# DOORLOCK_v4.net
KiCad netlist of a schematic drawn in EAGLE
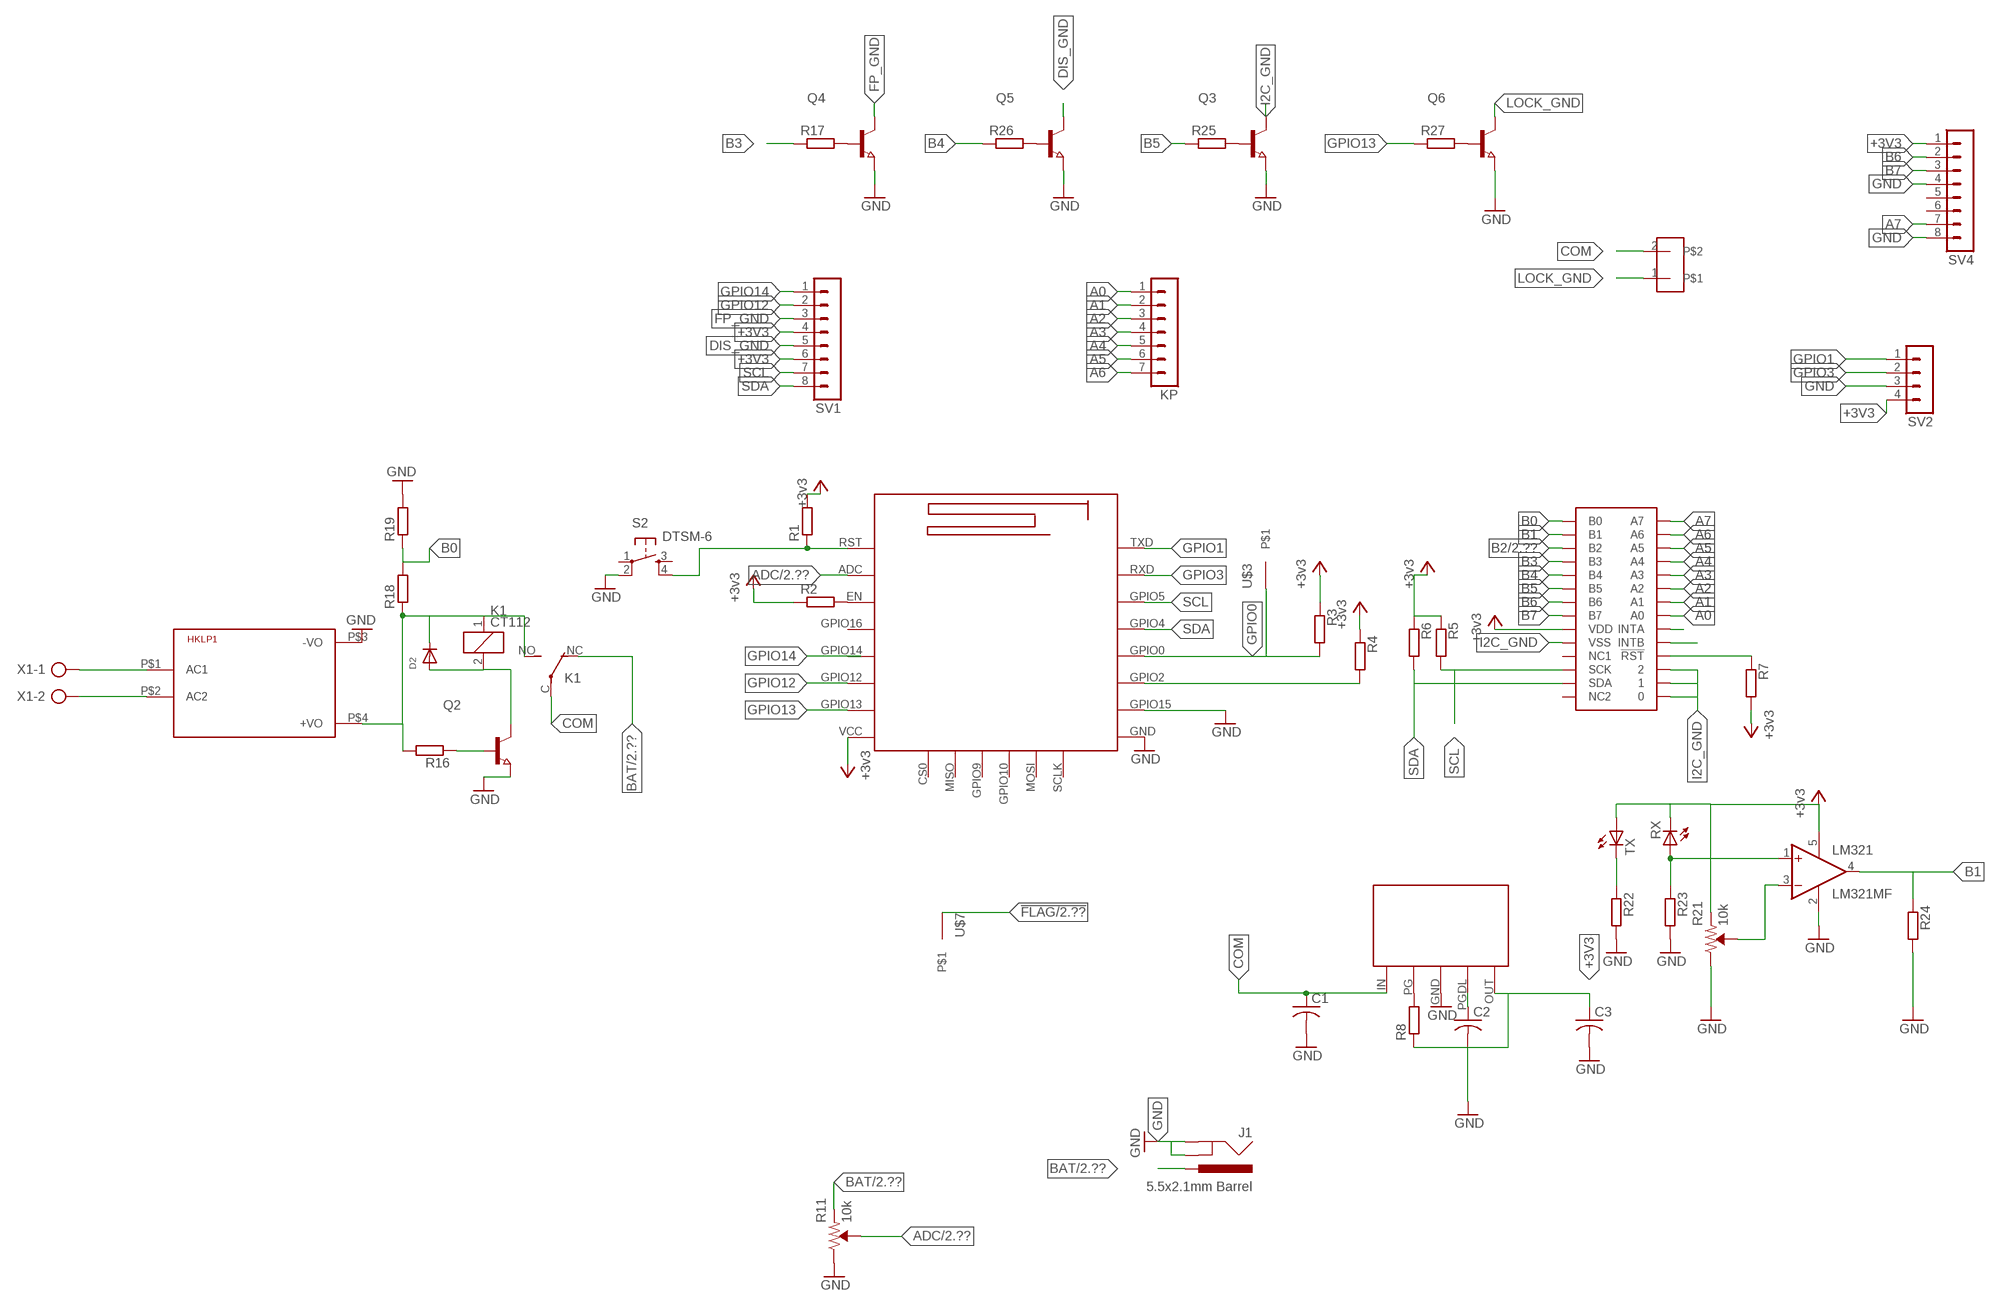
[diagram p0: schematic, sheet 1]
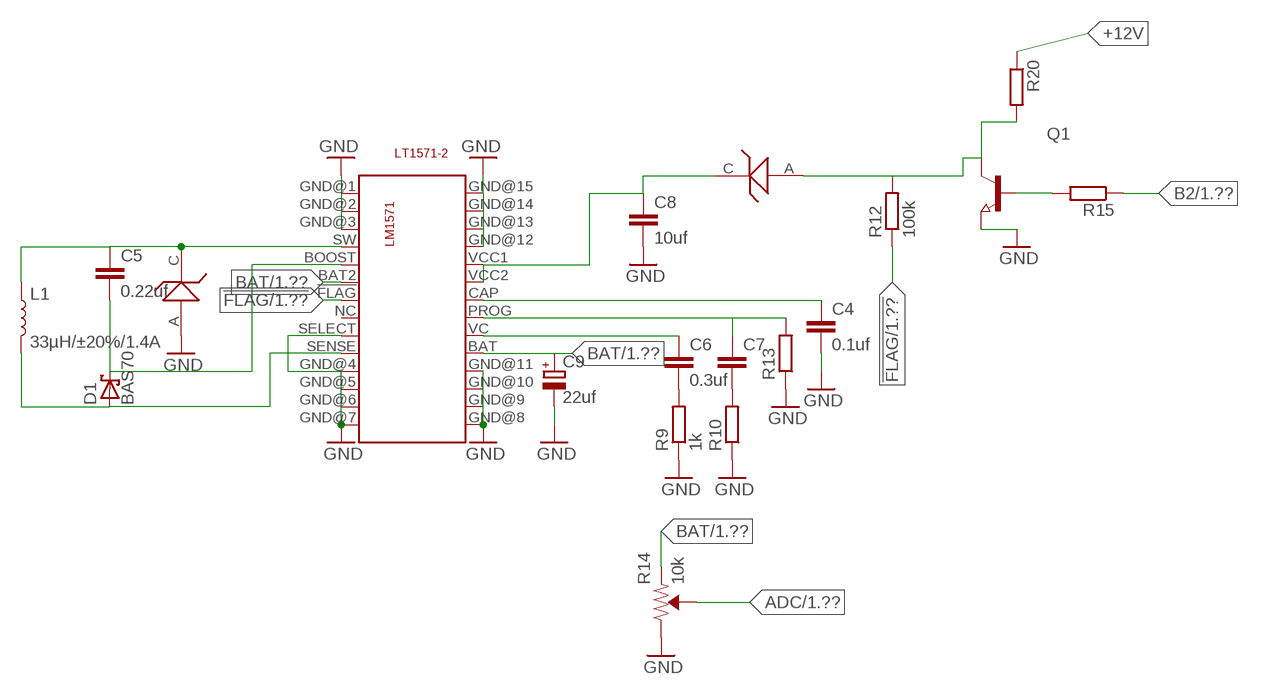
[diagram p1: schematic, sheet 2]

(export (version "E")
  (design (tool "Eeschema 10.0.6"))
  (components
    (comp (ref "C4")
      (value "0.1uf")
      (footprint "eagle-import:C0805")
      (libsource (lib "eagle-import") (part "C-EUC0805"))
    )
    (comp (ref "C5")
      (value "0.22uf")
      (footprint "eagle-import:C0805")
      (libsource (lib "eagle-import") (part "C-EUC0805"))
    )
    (comp (ref "C6")
      (value "0.3uf")
      (footprint "eagle-import:C0805")
      (libsource (lib "eagle-import") (part "C-EUC0805"))
    )
    (comp (ref "C7")
      (value "C-EUC0805")
      (footprint "eagle-import:C0805")
      (libsource (lib "eagle-import") (part "C-EUC0805"))
    )
    (comp (ref "C8")
      (value "10uf")
      (footprint "eagle-import:C0805")
      (libsource (lib "eagle-import") (part "C-EUC0805"))
    )
    (comp (ref "C9")
      (value "22uf")
      (footprint "eagle-import:CT3216")
      (libsource (lib "eagle-import") (part "CPOL-EUCT3216"))
    )
    (comp (ref "D1")
      (value "BAS70")
      (footprint "eagle-import:SOT23")
      (libsource (lib "eagle-import") (part "BAS70"))
    )
    (comp (ref "D3")
      (value "MBRM120T3")
      (footprint "eagle-import:MBRM120T3")
      (libsource (lib "eagle-import") (part "MBRM120T3"))
    )
    (comp (ref "L1")
      (value "33µH/±20%/1.4A")
      (footprint "eagle-import:SRN6045")
      (libsource (lib "eagle-import") (part "INDUCTOR-SRN6045-33UH"))
    )
    (comp (ref "LT1571-2")
      (value "LM1571")
      (footprint "eagle-import:LT1571")
      (libsource (lib "eagle-import") (part "LM1571"))
    )
    (comp (ref "Q1")
      (value "NPN-TRANSISTOR_SOT89")
      (footprint "eagle-import:SOT89")
      (libsource (lib "eagle-import") (part "NPN-TRANSISTOR_SOT89"))
    )
    (comp (ref "R9")
      (value "1k")
      (footprint "eagle-import:0204V")
      (libsource (lib "eagle-import") (part "R-EU_0204/2V"))
    )
    (comp (ref "R10")
      (value "R-EU_0204/2V")
      (footprint "eagle-import:0204V")
      (libsource (lib "eagle-import") (part "R-EU_0204/2V"))
    )
    (comp (ref "R12")
      (value "100k")
      (footprint "eagle-import:0204V")
      (libsource (lib "eagle-import") (part "R-EU_0204/2V"))
    )
    (comp (ref "R13")
      (value "R-EU_0204/2V")
      (footprint "eagle-import:0204V")
      (libsource (lib "eagle-import") (part "R-EU_0204/2V"))
    )
    (comp (ref "R14")
      (value "10k")
      (footprint "eagle-import:TRIMPOT-SMD-TC33X")
      (libsource (lib "eagle-import") (part "TRIMPOT-SMD-3MM-OPEN-1/10W-25%"))
    )
    (comp (ref "R15")
      (value "R-EU_0204/2V")
      (footprint "eagle-import:0204V")
      (libsource (lib "eagle-import") (part "R-EU_0204/2V"))
    )
    (comp (ref "R20")
      (value "R-EU_0204/2V")
      (footprint "eagle-import:0204V")
      (libsource (lib "eagle-import") (part "R-EU_0204/2V"))
    )
    (comp (ref "U$6")
      (value "MBRM120T3")
      (footprint "eagle-import:MBRM120T3")
      (libsource (lib "eagle-import") (part "MBRM120T3"))
    )
    (comp (ref "C1")
      (value "C-USC1206")
      (footprint "eagle-import:C1206")
      (libsource (lib "eagle-import") (part "C-USC1206"))
    )
    (comp (ref "C2")
      (value "C-USC1206")
      (footprint "eagle-import:C1206")
      (libsource (lib "eagle-import") (part "C-USC1206"))
    )
    (comp (ref "C3")
      (value "C-USC1206")
      (footprint "eagle-import:C1206")
      (libsource (lib "eagle-import") (part "C-USC1206"))
    )
    (comp (ref "D2")
      (value "DIODESOD-123")
      (footprint "eagle-import:SOD-123")
      (libsource (lib "eagle-import") (part "DIODESOD-123"))
    )
    (comp (ref "HKLP1")
      (value "HKLPM01")
      (footprint "eagle-import:HKLPM01")
      (libsource (lib "eagle-import") (part "HKLPM01"))
    )
    (comp (ref "J1")
      (value "5.5x2.1mm Barrel")
      (footprint "eagle-import:POWER_JACK_SMD")
      (libsource (lib "eagle-import") (part "POWER_JACKSMD"))
    )
    (comp (ref "K1")
      (value "CT112")
      (footprint "eagle-import:CT-SLIM")
      (libsource (lib "eagle-import") (part "CT112"))
    )
    (comp (ref "KP")
      (value "MA07-1")
      (footprint "eagle-import:MA07-1")
      (libsource (lib "eagle-import") (part "MA07-1"))
    )
    (comp (ref "LM321")
      (value "LM321MF")
      (footprint "eagle-import:SOT23-5")
      (libsource (lib "eagle-import") (part "LM321?MF"))
    )
    (comp (ref "MCP23017")
      (value "MCF23017")
      (footprint "eagle-import:MAX23017")
      (libsource (lib "eagle-import") (part "MCF23017"))
    )
    (comp (ref "MP2014")
      (value "MP2014")
      (footprint "eagle-import:MP2014")
      (libsource (lib "eagle-import") (part "MP2014"))
    )
    (comp (ref "Q2")
      (value "NPN-TRANSISTOR_SOT89")
      (footprint "eagle-import:SOT89")
      (libsource (lib "eagle-import") (part "NPN-TRANSISTOR_SOT89"))
    )
    (comp (ref "Q3")
      (value "NPN-TRANSISTOR_SOT89")
      (footprint "eagle-import:SOT89")
      (libsource (lib "eagle-import") (part "NPN-TRANSISTOR_SOT89"))
    )
    (comp (ref "Q4")
      (value "NPN-TRANSISTOR_SOT89")
      (footprint "eagle-import:SOT89")
      (libsource (lib "eagle-import") (part "NPN-TRANSISTOR_SOT89"))
    )
    (comp (ref "Q5")
      (value "NPN-TRANSISTOR_SOT89")
      (footprint "eagle-import:SOT89")
      (libsource (lib "eagle-import") (part "NPN-TRANSISTOR_SOT89"))
    )
    (comp (ref "Q6")
      (value "NPN-TRANSISTOR_SOT89")
      (footprint "eagle-import:SOT89")
      (libsource (lib "eagle-import") (part "NPN-TRANSISTOR_SOT89"))
    )
    (comp (ref "R1")
      (value "R-EU_0204/2V")
      (footprint "eagle-import:0204V")
      (libsource (lib "eagle-import") (part "resistor_R-EU_0204/2V"))
    )
    (comp (ref "R2")
      (value "R-EU_0204/2V")
      (footprint "eagle-import:0204V")
      (libsource (lib "eagle-import") (part "resistor_R-EU_0204/2V"))
    )
    (comp (ref "R3")
      (value "R-EU_0204/2V")
      (footprint "eagle-import:0204V")
      (libsource (lib "eagle-import") (part "resistor_R-EU_0204/2V"))
    )
    (comp (ref "R4")
      (value "R-EU_0204/2V")
      (footprint "eagle-import:0204V")
      (libsource (lib "eagle-import") (part "resistor_R-EU_0204/2V"))
    )
    (comp (ref "R5")
      (value "R-EU_0204/2V")
      (footprint "eagle-import:0204V")
      (libsource (lib "eagle-import") (part "resistor_R-EU_0204/2V"))
    )
    (comp (ref "R6")
      (value "R-EU_0204/2V")
      (footprint "eagle-import:0204V")
      (libsource (lib "eagle-import") (part "resistor_R-EU_0204/2V"))
    )
    (comp (ref "R7")
      (value "R-EU_0204/2V")
      (footprint "eagle-import:0204V")
      (libsource (lib "eagle-import") (part "resistor_R-EU_0204/2V"))
    )
    (comp (ref "R8")
      (value "R-EU_0204/2V")
      (footprint "eagle-import:0204V")
      (libsource (lib "eagle-import") (part "resistor_R-EU_0204/2V"))
    )
    (comp (ref "R11")
      (value "10k")
      (footprint "eagle-import:TRIMPOT-SMD-TC33X")
      (libsource (lib "eagle-import") (part "TRIMPOT-SMD-3MM-OPEN-1/10W-25%"))
    )
    (comp (ref "R16")
      (value "R-EU_0204/2V")
      (footprint "eagle-import:0204V")
      (libsource (lib "eagle-import") (part "resistor_R-EU_0204/2V"))
    )
    (comp (ref "R17")
      (value "R-EU_0204/2V")
      (footprint "eagle-import:0204V")
      (libsource (lib "eagle-import") (part "resistor_R-EU_0204/2V"))
    )
    (comp (ref "R18")
      (value "R-EU_0204/2V")
      (footprint "eagle-import:0204V")
      (libsource (lib "eagle-import") (part "resistor_R-EU_0204/2V"))
    )
    (comp (ref "R19")
      (value "R-EU_0204/2V")
      (footprint "eagle-import:0204V")
      (libsource (lib "eagle-import") (part "resistor_R-EU_0204/2V"))
    )
    (comp (ref "R21")
      (value "10k")
      (footprint "eagle-import:TRIMPOT-SMD-TC33X")
      (libsource (lib "eagle-import") (part "TRIMPOT-SMD-3MM-OPEN-1/10W-25%"))
    )
    (comp (ref "R22")
      (value "R-EU_0204/2V")
      (footprint "eagle-import:0204V")
      (libsource (lib "eagle-import") (part "resistor_R-EU_0204/2V"))
    )
    (comp (ref "R23")
      (value "R-EU_0204/2V")
      (footprint "eagle-import:0204V")
      (libsource (lib "eagle-import") (part "resistor_R-EU_0204/2V"))
    )
    (comp (ref "R24")
      (value "R-EU_0204/2V")
      (footprint "eagle-import:0204V")
      (libsource (lib "eagle-import") (part "resistor_R-EU_0204/2V"))
    )
    (comp (ref "R25")
      (value "R-EU_0204/2V")
      (footprint "eagle-import:0204V")
      (libsource (lib "eagle-import") (part "resistor_R-EU_0204/2V"))
    )
    (comp (ref "R26")
      (value "R-EU_0204/2V")
      (footprint "eagle-import:0204V")
      (libsource (lib "eagle-import") (part "resistor_R-EU_0204/2V"))
    )
    (comp (ref "R27")
      (value "R-EU_0204/2V")
      (footprint "eagle-import:0204V")
      (libsource (lib "eagle-import") (part "resistor_R-EU_0204/2V"))
    )
    (comp (ref "RX")
      (value "LED5MM")
      (footprint "eagle-import:LED5MM")
      (libsource (lib "eagle-import") (part "LED5MM"))
    )
    (comp (ref "S2")
      (value "DTSM-6")
      (footprint "eagle-import:DTSM-6")
      (libsource (lib "eagle-import") (part "DTSM-6"))
    )
    (comp (ref "SV1")
      (value "MA08-1")
      (footprint "eagle-import:MA08-1")
      (libsource (lib "eagle-import") (part "MA08-1"))
    )
    (comp (ref "SV2")
      (value "MA04-1")
      (footprint "eagle-import:MA04-1")
      (libsource (lib "eagle-import") (part "MA04-1"))
    )
    (comp (ref "SV4")
      (value "MA08-1")
      (footprint "eagle-import:MA08-1")
      (libsource (lib "eagle-import") (part "MA08-1"))
    )
    (comp (ref "TX")
      (value "LED5MM")
      (footprint "eagle-import:LED5MM")
      (libsource (lib "eagle-import") (part "LED5MM"))
    )
    (comp (ref "U$1")
      (value "ESP12E")
      (footprint "eagle-import:ESP-12E")
      (libsource (lib "eagle-import") (part "ESP12E"))
    )
    (comp (ref "U$3") (value "M1") (footprint "eagle-import:M1") (libsource (lib "eagle-import") (part "M1")))
    (comp (ref "U$4")
      (value "MALE2PIN")
      (footprint "eagle-import:MALE2PIN")
      (libsource (lib "eagle-import") (part "MALE2PIN"))
    )
    (comp (ref "U$7") (value "M1") (footprint "eagle-import:M1") (libsource (lib "eagle-import") (part "M1")))
    (comp (ref "X1")
      (value "AK500/2-H")
      (footprint "eagle-import:AK500_2-H")
      (libsource (lib "eagle-import") (part "AK500/2-H"))
    )
  )
  (nets
    (net (code "1") (name "+3V3") (class "Default")
      (node (ref "C3") (pin "1") (pinfunction "1_1") (pintype "passive"))
      (node (ref "LM321") (pin "5") (pinfunction "V+_5") (pintype "power_in"))
      (node (ref "MCP23017") (pin "P$9") (pinfunction "VDD_P$9") (pintype "bidirectional"))
      (node (ref "MP2014") (pin "OUT") (pinfunction "P$5_OUT") (pintype "bidirectional"))
      (node (ref "R1") (pin "2") (pinfunction "2_2") (pintype "passive"))
      (node (ref "R2") (pin "1") (pinfunction "1_1") (pintype "passive"))
      (node (ref "R21") (pin "3") (pinfunction "CCW_3") (pintype "passive"))
      (node (ref "R3") (pin "1") (pinfunction "1_1") (pintype "passive"))
      (node (ref "R4") (pin "1") (pinfunction "1_1") (pintype "passive"))
      (node (ref "R5") (pin "1") (pinfunction "1_1") (pintype "passive"))
      (node (ref "R6") (pin "1") (pinfunction "1_1") (pintype "passive"))
      (node (ref "R7") (pin "2") (pinfunction "2_2") (pintype "passive"))
      (node (ref "R8") (pin "1") (pinfunction "1_1") (pintype "passive"))
      (node (ref "RX") (pin "K") (pinfunction "C_K") (pintype "passive"))
      (node (ref "SV1") (pin "4") (pinfunction "4_4") (pintype "passive"))
      (node (ref "SV1") (pin "6") (pinfunction "6_6") (pintype "passive"))
      (node (ref "SV2") (pin "4") (pinfunction "4_4") (pintype "passive"))
      (node (ref "SV4") (pin "1") (pinfunction "1_1") (pintype "passive"))
      (node (ref "TX") (pin "A") (pinfunction "A_A") (pintype "passive"))
      (node (ref "U$1") (pin "VCC") (pinfunction "P$8_VCC") (pintype "bidirectional"))
    )
    (net (code "2") (name "+12V") (class "Default")
      (node (ref "D2") (pin "C") (pinfunction "C_C") (pintype "passive"))
      (node (ref "HKLP1") (pin "P$4") (pinfunction "+VO_P$4") (pintype "bidirectional"))
      (node (ref "K1") (pin "1") (pinfunction "1_1") (pintype "passive"))
      (node (ref "K1") (pin "NO") (pinfunction "S_NO") (pintype "passive"))
      (node (ref "R16") (pin "2") (pinfunction "2_2") (pintype "passive"))
      (node (ref "R18") (pin "1") (pinfunction "1_1") (pintype "passive"))
      (node (ref "R20") (pin "1") (pinfunction "1_1") (pintype "passive"))
    )
    (net (code "3") (name "A0") (class "Default")
      (node (ref "KP") (pin "1") (pinfunction "1_1") (pintype "passive"))
      (node (ref "MCP23017") (pin "P$21") (pinfunction "A0_P$21") (pintype "bidirectional"))
    )
    (net (code "4") (name "A1") (class "Default")
      (node (ref "KP") (pin "2") (pinfunction "2_2") (pintype "passive"))
      (node (ref "MCP23017") (pin "P$22") (pinfunction "A1_P$22") (pintype "bidirectional"))
    )
    (net (code "5") (name "A2") (class "Default")
      (node (ref "KP") (pin "3") (pinfunction "3_3") (pintype "passive"))
      (node (ref "MCP23017") (pin "P$23") (pinfunction "A2_P$23") (pintype "bidirectional"))
    )
    (net (code "6") (name "A3") (class "Default")
      (node (ref "KP") (pin "4") (pinfunction "4_4") (pintype "passive"))
      (node (ref "MCP23017") (pin "P$24") (pinfunction "A3_P$24") (pintype "bidirectional"))
    )
    (net (code "7") (name "A4") (class "Default")
      (node (ref "KP") (pin "5") (pinfunction "5_5") (pintype "passive"))
      (node (ref "MCP23017") (pin "P$25") (pinfunction "A4_P$25") (pintype "bidirectional"))
    )
    (net (code "8") (name "A5") (class "Default")
      (node (ref "KP") (pin "6") (pinfunction "6_6") (pintype "passive"))
      (node (ref "MCP23017") (pin "P$26") (pinfunction "A5_P$26") (pintype "bidirectional"))
    )
    (net (code "9") (name "A6") (class "Default")
      (node (ref "KP") (pin "7") (pinfunction "7_7") (pintype "passive"))
      (node (ref "MCP23017") (pin "P$27") (pinfunction "A6_P$27") (pintype "bidirectional"))
    )
    (net (code "10") (name "A7") (class "Default")
      (node (ref "MCP23017") (pin "P$28") (pinfunction "A7_P$28") (pintype "bidirectional"))
      (node (ref "SV4") (pin "7") (pinfunction "7_7") (pintype "passive"))
    )
    (net (code "11") (name "ADC") (class "Default")
      (node (ref "R11") (pin "2") (pinfunction "WIPER_2") (pintype "passive"))
      (node (ref "R14") (pin "2") (pinfunction "WIPER_2") (pintype "passive"))
      (node (ref "U$1") (pin "ADC") (pinfunction "P$2_ADC") (pintype "bidirectional"))
    )
    (net (code "12") (name "B0") (class "Default")
      (node (ref "MCP23017") (pin "P$1") (pinfunction "B0_P$1") (pintype "bidirectional"))
      (node (ref "R18") (pin "2") (pinfunction "2_2") (pintype "passive"))
      (node (ref "R19") (pin "1") (pinfunction "1_1") (pintype "passive"))
    )
    (net (code "13") (name "B1") (class "Default")
      (node (ref "LM321") (pin "4") (pinfunction "OUT_4") (pintype "output"))
      (node (ref "MCP23017") (pin "P$2") (pinfunction "B1_P$2") (pintype "bidirectional"))
      (node (ref "R24") (pin "1") (pinfunction "1_1") (pintype "passive"))
    )
    (net (code "14") (name "B2") (class "Default")
      (node (ref "MCP23017") (pin "P$3") (pinfunction "B2_P$3") (pintype "bidirectional"))
      (node (ref "R15") (pin "1") (pinfunction "1_1") (pintype "passive"))
    )
    (net (code "15") (name "B3") (class "Default")
      (node (ref "MCP23017") (pin "P$4") (pinfunction "B3_P$4") (pintype "bidirectional"))
      (node (ref "R17") (pin "1") (pinfunction "1_1") (pintype "passive"))
    )
    (net (code "16") (name "B4") (class "Default")
      (node (ref "MCP23017") (pin "P$5") (pinfunction "B4_P$5") (pintype "bidirectional"))
      (node (ref "R26") (pin "1") (pinfunction "1_1") (pintype "passive"))
    )
    (net (code "17") (name "B5") (class "Default")
      (node (ref "MCP23017") (pin "P$6") (pinfunction "B5_P$6") (pintype "bidirectional"))
      (node (ref "R25") (pin "1") (pinfunction "1_1") (pintype "passive"))
    )
    (net (code "18") (name "B6") (class "Default")
      (node (ref "MCP23017") (pin "P$7") (pinfunction "B6_P$7") (pintype "bidirectional"))
      (node (ref "SV4") (pin "2") (pinfunction "2_2") (pintype "passive"))
    )
    (net (code "19") (name "B7") (class "Default")
      (node (ref "MCP23017") (pin "P$8") (pinfunction "B7_P$8") (pintype "bidirectional"))
      (node (ref "SV4") (pin "3") (pinfunction "3_3") (pintype "passive"))
    )
    (net (code "20") (name "BAT") (class "Default")
      (node (ref "C9") (pin "+") (pinfunction "+_+") (pintype "passive"))
      (node (ref "J1") (pin "VIN0") (pinfunction "PWR_VIN0") (pintype "bidirectional"))
      (node (ref "K1") (pin "NC") (pinfunction "O_NC") (pintype "passive"))
      (node (ref "LT1571-2") (pin "BAT") (pinfunction "P$19_BAT") (pintype "bidirectional"))
      (node (ref "LT1571-2") (pin "BAT2") (pinfunction "P$6_BAT2") (pintype "bidirectional"))
      (node (ref "R11") (pin "3") (pinfunction "CCW_3") (pintype "passive"))
      (node (ref "R14") (pin "3") (pinfunction "CCW_3") (pintype "passive"))
    )
    (net (code "21") (name "COM") (class "Default")
      (node (ref "C1") (pin "1") (pinfunction "1_1") (pintype "passive"))
      (node (ref "K1") (pin "C") (pinfunction "P_C") (pintype "passive"))
      (node (ref "MP2014") (pin "IN") (pinfunction "P$1_IN") (pintype "bidirectional"))
      (node (ref "U$4") (pin "2") (pinfunction "P$2_2") (pintype "bidirectional"))
    )
    (net (code "22") (name "DIS_GND") (class "Default")
      (node (ref "Q5") (pin "2") (pinfunction "C_2") (pintype "passive"))
      (node (ref "SV1") (pin "5") (pinfunction "5_5") (pintype "passive"))
    )
    (net (code "23") (name "FP_GND") (class "Default")
      (node (ref "Q4") (pin "2") (pinfunction "C_2") (pintype "passive"))
      (node (ref "SV1") (pin "3") (pinfunction "3_3") (pintype "passive"))
    )
    (net (code "24") (name "GND") (class "Default")
      (node (ref "C1") (pin "2") (pinfunction "2_2") (pintype "passive"))
      (node (ref "C2") (pin "2") (pinfunction "2_2") (pintype "passive"))
      (node (ref "C3") (pin "2") (pinfunction "2_2") (pintype "passive"))
      (node (ref "C4") (pin "2") (pinfunction "2_2") (pintype "passive"))
      (node (ref "C8") (pin "2") (pinfunction "2_2") (pintype "passive"))
      (node (ref "C9") (pin "-") (pinfunction "-_-") (pintype "passive"))
      (node (ref "HKLP1") (pin "P$3") (pinfunction "-VO_P$3") (pintype "bidirectional"))
      (node (ref "J1") (pin "GND") (pinfunction "GNDBREAK_GND") (pintype "bidirectional"))
      (node (ref "J1") (pin "P$4") (pinfunction "GND_P$4") (pintype "bidirectional"))
      (node (ref "LM321") (pin "2") (pinfunction "V-_2") (pintype "power_in"))
      (node (ref "LT1571-2") (pin "GND@1") (pinfunction "P$1_GND@1") (pintype "bidirectional"))
      (node (ref "LT1571-2") (pin "GND@10") (pinfunction "P$17_GND@10") (pintype "bidirectional"))
      (node (ref "LT1571-2") (pin "GND@11") (pinfunction "P$18_GND@11") (pintype "bidirectional"))
      (node (ref "LT1571-2") (pin "GND@12") (pinfunction "P$25_GND@12") (pintype "bidirectional"))
      (node (ref "LT1571-2") (pin "GND@13") (pinfunction "P$26_GND@13") (pintype "bidirectional"))
      (node (ref "LT1571-2") (pin "GND@14") (pinfunction "P$27_GND@14") (pintype "bidirectional"))
      (node (ref "LT1571-2") (pin "GND@15") (pinfunction "P$28_GND@15") (pintype "bidirectional"))
      (node (ref "LT1571-2") (pin "GND@2") (pinfunction "P$2_GND@2") (pintype "bidirectional"))
      (node (ref "LT1571-2") (pin "GND@3") (pinfunction "P$3_GND@3") (pintype "bidirectional"))
      (node (ref "LT1571-2") (pin "GND@4") (pinfunction "P$11_GND@4") (pintype "bidirectional"))
      (node (ref "LT1571-2") (pin "GND@5") (pinfunction "P$12_GND@5") (pintype "bidirectional"))
      (node (ref "LT1571-2") (pin "GND@6") (pinfunction "P$13_GND@6") (pintype "bidirectional"))
      (node (ref "LT1571-2") (pin "GND@7") (pinfunction "P$14_GND@7") (pintype "bidirectional"))
      (node (ref "LT1571-2") (pin "GND@8") (pinfunction "P$15_GND@8") (pintype "bidirectional"))
      (node (ref "LT1571-2") (pin "GND@9") (pinfunction "P$16_GND@9") (pintype "bidirectional"))
      (node (ref "LT1571-2") (pin "SELECT") (pinfunction "P$9_SELECT") (pintype "bidirectional"))
      (node (ref "MP2014") (pin "GND") (pinfunction "P$3_GND") (pintype "bidirectional"))
      (node (ref "Q1") (pin "3") (pinfunction "E_3") (pintype "passive"))
      (node (ref "Q2") (pin "3") (pinfunction "E_3") (pintype "passive"))
      (node (ref "Q3") (pin "3") (pinfunction "E_3") (pintype "passive"))
      (node (ref "Q4") (pin "3") (pinfunction "E_3") (pintype "passive"))
      (node (ref "Q5") (pin "3") (pinfunction "E_3") (pintype "passive"))
      (node (ref "Q6") (pin "3") (pinfunction "E_3") (pintype "passive"))
      (node (ref "R10") (pin "1") (pinfunction "1_1") (pintype "passive"))
      (node (ref "R11") (pin "1") (pinfunction "CW_1") (pintype "passive"))
      (node (ref "R13") (pin "1") (pinfunction "1_1") (pintype "passive"))
      (node (ref "R14") (pin "1") (pinfunction "CW_1") (pintype "passive"))
      (node (ref "R19") (pin "2") (pinfunction "2_2") (pintype "passive"))
      (node (ref "R21") (pin "1") (pinfunction "CW_1") (pintype "passive"))
      (node (ref "R22") (pin "2") (pinfunction "2_2") (pintype "passive"))
      (node (ref "R23") (pin "2") (pinfunction "2_2") (pintype "passive"))
      (node (ref "R24") (pin "2") (pinfunction "2_2") (pintype "passive"))
      (node (ref "R9") (pin "1") (pinfunction "1_1") (pintype "passive"))
      (node (ref "S2") (pin "2") (pinfunction "2_2") (pintype "passive"))
      (node (ref "SV2") (pin "3") (pinfunction "3_3") (pintype "passive"))
      (node (ref "SV4") (pin "4") (pinfunction "4_4") (pintype "passive"))
      (node (ref "SV4") (pin "8") (pinfunction "8_8") (pintype "passive"))
      (node (ref "U$1") (pin "GND") (pinfunction "P$15_GND") (pintype "bidirectional"))
      (node (ref "U$1") (pin "GPIO15") (pinfunction "P$16_GPIO15") (pintype "bidirectional"))
      (node (ref "U$6") (pin "A") (pinfunction "A_A") (pintype "bidirectional"))
    )
    (net (code "25") (name "GPIO0") (class "Default")
      (node (ref "R3") (pin "2") (pinfunction "2_2") (pintype "passive"))
      (node (ref "U$1") (pin "GPIO0") (pinfunction "P$18_GPIO0") (pintype "bidirectional"))
      (node (ref "U$3") (pin "P$1") (pinfunction "P$1_P$1") (pintype "bidirectional"))
    )
    (net (code "26") (name "GPIO1") (class "Default")
      (node (ref "SV2") (pin "1") (pinfunction "1_1") (pintype "passive"))
      (node (ref "U$1") (pin "TXD") (pinfunction "P$22_TXD") (pintype "bidirectional"))
    )
    (net (code "27") (name "GPIO3") (class "Default")
      (node (ref "SV2") (pin "2") (pinfunction "2_2") (pintype "passive"))
      (node (ref "U$1") (pin "RXD") (pinfunction "P$21_RXD") (pintype "bidirectional"))
    )
    (net (code "28") (name "GPIO12") (class "Default")
      (node (ref "SV1") (pin "2") (pinfunction "2_2") (pintype "passive"))
      (node (ref "U$1") (pin "GPIO12") (pinfunction "P$6_GPIO12") (pintype "bidirectional"))
    )
    (net (code "29") (name "GPIO13") (class "Default")
      (node (ref "R27") (pin "1") (pinfunction "1_1") (pintype "passive"))
      (node (ref "U$1") (pin "GPIO13") (pinfunction "P$7_GPIO13") (pintype "bidirectional"))
    )
    (net (code "30") (name "GPIO14") (class "Default")
      (node (ref "SV1") (pin "1") (pinfunction "1_1") (pintype "passive"))
      (node (ref "U$1") (pin "GPIO14") (pinfunction "P$5_GPIO14") (pintype "bidirectional"))
    )
    (net (code "31") (name "I2C_GND") (class "Default")
      (node (ref "MCP23017") (pin "P$10") (pinfunction "VSS_P$10") (pintype "bidirectional"))
      (node (ref "MCP23017") (pin "P$15") (pinfunction "0_P$15") (pintype "bidirectional"))
      (node (ref "MCP23017") (pin "P$16") (pinfunction "1_P$16") (pintype "bidirectional"))
      (node (ref "MCP23017") (pin "P$17") (pinfunction "2_P$17") (pintype "bidirectional"))
      (node (ref "Q3") (pin "2") (pinfunction "C_2") (pintype "passive"))
    )
    (net (code "32") (name "LOCK_GND") (class "Default")
      (node (ref "Q6") (pin "2") (pinfunction "C_2") (pintype "passive"))
      (node (ref "U$4") (pin "1") (pinfunction "P$1_1") (pintype "bidirectional"))
    )
    (net (code "33") (name "Net-(C6-Pad2)") (class "Default")
      (node (ref "C6") (pin "2") (pinfunction "2_2") (pintype "passive"))
      (node (ref "R9") (pin "2") (pinfunction "2_2") (pintype "passive"))
    )
    (net (code "34") (name "Net-(C7-Pad2)") (class "Default")
      (node (ref "C7") (pin "2") (pinfunction "2_2") (pintype "passive"))
      (node (ref "R10") (pin "2") (pinfunction "2_2") (pintype "passive"))
    )
    (net (code "35") (name "Net-(D1-A)") (class "Default")
      (node (ref "D1") (pin "1") (pinfunction "A_1") (pintype "passive"))
      (node (ref "L1") (pin "2") (pinfunction "2_2") (pintype "passive"))
      (node (ref "LT1571-2") (pin "SENSE") (pinfunction "P$10_SENSE") (pintype "bidirectional"))
    )
    (net (code "36") (name "Net-(D1-C)") (class "Default")
      (node (ref "C5") (pin "2") (pinfunction "2_2") (pintype "passive"))
      (node (ref "D1") (pin "3") (pinfunction "C_3") (pintype "passive"))
      (node (ref "LT1571-2") (pin "BOOST") (pinfunction "P$5_BOOST") (pintype "bidirectional"))
    )
    (net (code "37") (name "Net-(HKLP1-AC1)") (class "Default")
      (node (ref "HKLP1") (pin "P$1") (pinfunction "AC1_P$1") (pintype "bidirectional"))
      (node (ref "X1") (pin "1") (pinfunction "KL_1") (pintype "passive"))
    )
    (net (code "38") (name "Net-(HKLP1-AC2)") (class "Default")
      (node (ref "HKLP1") (pin "P$2") (pinfunction "AC2_P$2") (pintype "bidirectional"))
      (node (ref "X1") (pin "2") (pinfunction "KL_2") (pintype "passive"))
    )
    (net (code "39") (name "Net-(LM321-+IN)") (class "Default")
      (node (ref "LM321") (pin "1") (pinfunction "+IN_1") (pintype "input"))
      (node (ref "R23") (pin "1") (pinfunction "1_1") (pintype "passive"))
      (node (ref "RX") (pin "A") (pinfunction "A_A") (pintype "passive"))
    )
    (net (code "40") (name "Net-(LM321--IN)") (class "Default")
      (node (ref "LM321") (pin "3") (pinfunction "-IN_3") (pintype "input"))
      (node (ref "R21") (pin "2") (pinfunction "WIPER_2") (pintype "passive"))
    )
    (net (code "41") (name "Net-(LT1571-2-P$4)") (class "Default")
      (node (ref "C5") (pin "1") (pinfunction "1_1") (pintype "passive"))
      (node (ref "L1") (pin "1") (pinfunction "1_1") (pintype "passive"))
      (node (ref "LT1571-2") (pin "SW") (pinfunction "P$4_SW") (pintype "bidirectional"))
      (node (ref "U$6") (pin "C") (pinfunction "C_C") (pintype "bidirectional"))
    )
    (net (code "42") (name "Net-(LT1571-2-P$20)") (class "Default")
      (node (ref "C6") (pin "1") (pinfunction "1_1") (pintype "passive"))
      (node (ref "LT1571-2") (pin "VC") (pinfunction "P$20_VC") (pintype "bidirectional"))
    )
    (net (code "43") (name "Net-(LT1571-2-P$21)") (class "Default")
      (node (ref "C7") (pin "1") (pinfunction "1_1") (pintype "passive"))
      (node (ref "LT1571-2") (pin "PROG") (pinfunction "P$21_PROG") (pintype "bidirectional"))
      (node (ref "R13") (pin "2") (pinfunction "2_2") (pintype "passive"))
    )
    (net (code "44") (name "Net-(LT1571-2-P$22)") (class "Default")
      (node (ref "C4") (pin "1") (pinfunction "1_1") (pintype "passive"))
      (node (ref "LT1571-2") (pin "CAP") (pinfunction "P$22_CAP") (pintype "bidirectional"))
    )
    (net (code "45") (name "Net-(LT1571-2-P$23)") (class "Default")
      (node (ref "C8") (pin "1") (pinfunction "1_1") (pintype "passive"))
      (node (ref "D3") (pin "C") (pinfunction "C_C") (pintype "bidirectional"))
      (node (ref "LT1571-2") (pin "VCC1") (pinfunction "P$24_VCC1") (pintype "bidirectional"))
      (node (ref "LT1571-2") (pin "VCC2") (pinfunction "P$23_VCC2") (pintype "bidirectional"))
    )
    (net (code "46") (name "Net-(MCP23017-~{RST})") (class "Default")
      (node (ref "MCP23017") (pin "P$18") (pinfunction "~{RST}_P$18") (pintype "bidirectional"))
      (node (ref "R7") (pin "1") (pinfunction "1_1") (pintype "passive"))
    )
    (net (code "47") (name "Net-(MP2014-P$2)") (class "Default")
      (node (ref "MP2014") (pin "PG") (pinfunction "P$2_PG") (pintype "bidirectional"))
      (node (ref "R8") (pin "2") (pinfunction "2_2") (pintype "passive"))
    )
    (net (code "48") (name "Net-(MP2014-P$4)") (class "Default")
      (node (ref "C2") (pin "1") (pinfunction "1_1") (pintype "passive"))
      (node (ref "MP2014") (pin "PGDL") (pinfunction "P$4_PGDL") (pintype "bidirectional"))
    )
    (net (code "49") (name "Net-(Q1-B)") (class "Default")
      (node (ref "Q1") (pin "1") (pinfunction "B_1") (pintype "passive"))
      (node (ref "R15") (pin "2") (pinfunction "2_2") (pintype "passive"))
    )
    (net (code "50") (name "Net-(Q1-C)") (class "Default")
      (node (ref "D3") (pin "A") (pinfunction "A_A") (pintype "bidirectional"))
      (node (ref "Q1") (pin "2") (pinfunction "C_2") (pintype "passive"))
      (node (ref "R12") (pin "2") (pinfunction "2_2") (pintype "passive"))
      (node (ref "R20") (pin "2") (pinfunction "2_2") (pintype "passive"))
    )
    (net (code "51") (name "Net-(Q2-B)") (class "Default")
      (node (ref "Q2") (pin "1") (pinfunction "B_1") (pintype "passive"))
      (node (ref "R16") (pin "1") (pinfunction "1_1") (pintype "passive"))
    )
    (net (code "52") (name "Net-(Q2-C)") (class "Default")
      (node (ref "D2") (pin "A") (pinfunction "A_A") (pintype "passive"))
      (node (ref "K1") (pin "2") (pinfunction "2_2") (pintype "passive"))
      (node (ref "Q2") (pin "2") (pinfunction "C_2") (pintype "passive"))
    )
    (net (code "53") (name "Net-(Q3-B)") (class "Default")
      (node (ref "Q3") (pin "1") (pinfunction "B_1") (pintype "passive"))
      (node (ref "R25") (pin "2") (pinfunction "2_2") (pintype "passive"))
    )
    (net (code "54") (name "Net-(Q4-B)") (class "Default")
      (node (ref "Q4") (pin "1") (pinfunction "B_1") (pintype "passive"))
      (node (ref "R17") (pin "2") (pinfunction "2_2") (pintype "passive"))
    )
    (net (code "55") (name "Net-(Q5-B)") (class "Default")
      (node (ref "Q5") (pin "1") (pinfunction "B_1") (pintype "passive"))
      (node (ref "R26") (pin "2") (pinfunction "2_2") (pintype "passive"))
    )
    (net (code "56") (name "Net-(Q6-B)") (class "Default")
      (node (ref "Q6") (pin "1") (pinfunction "B_1") (pintype "passive"))
      (node (ref "R27") (pin "2") (pinfunction "2_2") (pintype "passive"))
    )
    (net (code "57") (name "Net-(TX-C)") (class "Default")
      (node (ref "R22") (pin "1") (pinfunction "1_1") (pintype "passive"))
      (node (ref "TX") (pin "K") (pinfunction "C_K") (pintype "passive"))
    )
    (net (code "58") (name "Net-(U$1-P$1)") (class "Default")
      (node (ref "R1") (pin "1") (pinfunction "1_1") (pintype "passive"))
      (node (ref "S2") (pin "4") (pinfunction "4_4") (pintype "passive"))
      (node (ref "U$1") (pin "RST") (pinfunction "P$1_RST") (pintype "bidirectional"))
    )
    (net (code "59") (name "Net-(U$1-P$3)") (class "Default")
      (node (ref "R2") (pin "2") (pinfunction "2_2") (pintype "passive"))
      (node (ref "U$1") (pin "EN") (pinfunction "P$3_EN") (pintype "bidirectional"))
    )
    (net (code "60") (name "Net-(U$1-P$17)") (class "Default")
      (node (ref "R4") (pin "2") (pinfunction "2_2") (pintype "passive"))
      (node (ref "U$1") (pin "GPIO2") (pinfunction "P$17_GPIO2") (pintype "bidirectional"))
    )
    (net (code "61") (name "SCL") (class "Default")
      (node (ref "MCP23017") (pin "P$12") (pinfunction "SCK_P$12") (pintype "bidirectional"))
      (node (ref "R5") (pin "2") (pinfunction "2_2") (pintype "passive"))
      (node (ref "SV1") (pin "7") (pinfunction "7_7") (pintype "passive"))
      (node (ref "U$1") (pin "GPIO5") (pinfunction "P$20_GPIO5") (pintype "bidirectional"))
    )
    (net (code "62") (name "SDA") (class "Default")
      (node (ref "MCP23017") (pin "P$13") (pinfunction "SDA_P$13") (pintype "bidirectional"))
      (node (ref "R6") (pin "2") (pinfunction "2_2") (pintype "passive"))
      (node (ref "SV1") (pin "8") (pinfunction "8_8") (pintype "passive"))
      (node (ref "U$1") (pin "GPIO4") (pinfunction "P$19_GPIO4") (pintype "bidirectional"))
    )
    (net (code "63") (name "unconnected-(LT1571-2-P$8-PadNC)") (class "Default")
      (node (ref "LT1571-2") (pin "NC") (pinfunction "P$8_NC") (pintype "bidirectional"))
    )
    (net (code "64") (name "unconnected-(MCP23017-INTA-PadP$20)") (class "Default")
      (node (ref "MCP23017") (pin "P$20") (pinfunction "INTA_P$20") (pintype "bidirectional"))
    )
    (net (code "65") (name "unconnected-(MCP23017-INTB-PadP$19)") (class "Default")
      (node (ref "MCP23017") (pin "P$19") (pinfunction "INTB_P$19") (pintype "bidirectional"))
    )
    (net (code "66") (name "unconnected-(MCP23017-NC1-PadP$11)") (class "Default")
      (node (ref "MCP23017") (pin "P$11") (pinfunction "NC1_P$11") (pintype "bidirectional"))
    )
    (net (code "67") (name "unconnected-(MCP23017-NC2-PadP$14)") (class "Default")
      (node (ref "MCP23017") (pin "P$14") (pinfunction "NC2_P$14") (pintype "bidirectional"))
    )
    (net (code "68") (name "unconnected-(S2-Pad1)") (class "Default")
      (node (ref "S2") (pin "1") (pinfunction "1_1") (pintype "passive"))
    )
    (net (code "69") (name "unconnected-(S2-Pad3)") (class "Default")
      (node (ref "S2") (pin "3") (pinfunction "3_3") (pintype "passive"))
    )
    (net (code "70") (name "unconnected-(SV4-Pad5)") (class "Default")
      (node (ref "SV4") (pin "5") (pinfunction "5_5") (pintype "passive"))
    )
    (net (code "71") (name "unconnected-(SV4-Pad6)") (class "Default")
      (node (ref "SV4") (pin "6") (pinfunction "6_6") (pintype "passive"))
    )
    (net (code "72") (name "unconnected-(U$1-P$4-PadGPIO16)") (class "Default")
      (node (ref "U$1") (pin "GPIO16") (pinfunction "P$4_GPIO16") (pintype "bidirectional"))
    )
    (net (code "73") (name "unconnected-(U$1-P$9-PadCS0)") (class "Default")
      (node (ref "U$1") (pin "CS0") (pinfunction "P$9_CS0") (pintype "bidirectional"))
    )
    (net (code "74") (name "unconnected-(U$1-P$10-PadMISO)") (class "Default")
      (node (ref "U$1") (pin "MISO") (pinfunction "P$10_MISO") (pintype "bidirectional"))
    )
    (net (code "75") (name "unconnected-(U$1-P$11-PadGPIO9)") (class "Default")
      (node (ref "U$1") (pin "GPIO9") (pinfunction "P$11_GPIO9") (pintype "bidirectional"))
    )
    (net (code "76") (name "unconnected-(U$1-P$12-PadGPIO10)") (class "Default")
      (node (ref "U$1") (pin "GPIO10") (pinfunction "P$12_GPIO10") (pintype "bidirectional"))
    )
    (net (code "77") (name "unconnected-(U$1-P$13-PadMOSI)") (class "Default")
      (node (ref "U$1") (pin "MOSI") (pinfunction "P$13_MOSI") (pintype "bidirectional"))
    )
    (net (code "78") (name "unconnected-(U$1-P$14-PadSCLK)") (class "Default")
      (node (ref "U$1") (pin "SCLK") (pinfunction "P$14_SCLK") (pintype "bidirectional"))
    )
    (net (code "79") (name "~{FLAG}") (class "Default")
      (node (ref "LT1571-2") (pin "!FLAG") (pinfunction "P$7_!FLAG") (pintype "bidirectional"))
      (node (ref "R12") (pin "1") (pinfunction "1_1") (pintype "passive"))
      (node (ref "U$7") (pin "P$1") (pinfunction "P$1_P$1") (pintype "bidirectional"))
    )
  )
)
